# EXPRESS_BYOG_Shield.net
KiCad netlist of a schematic drawn in EAGLE
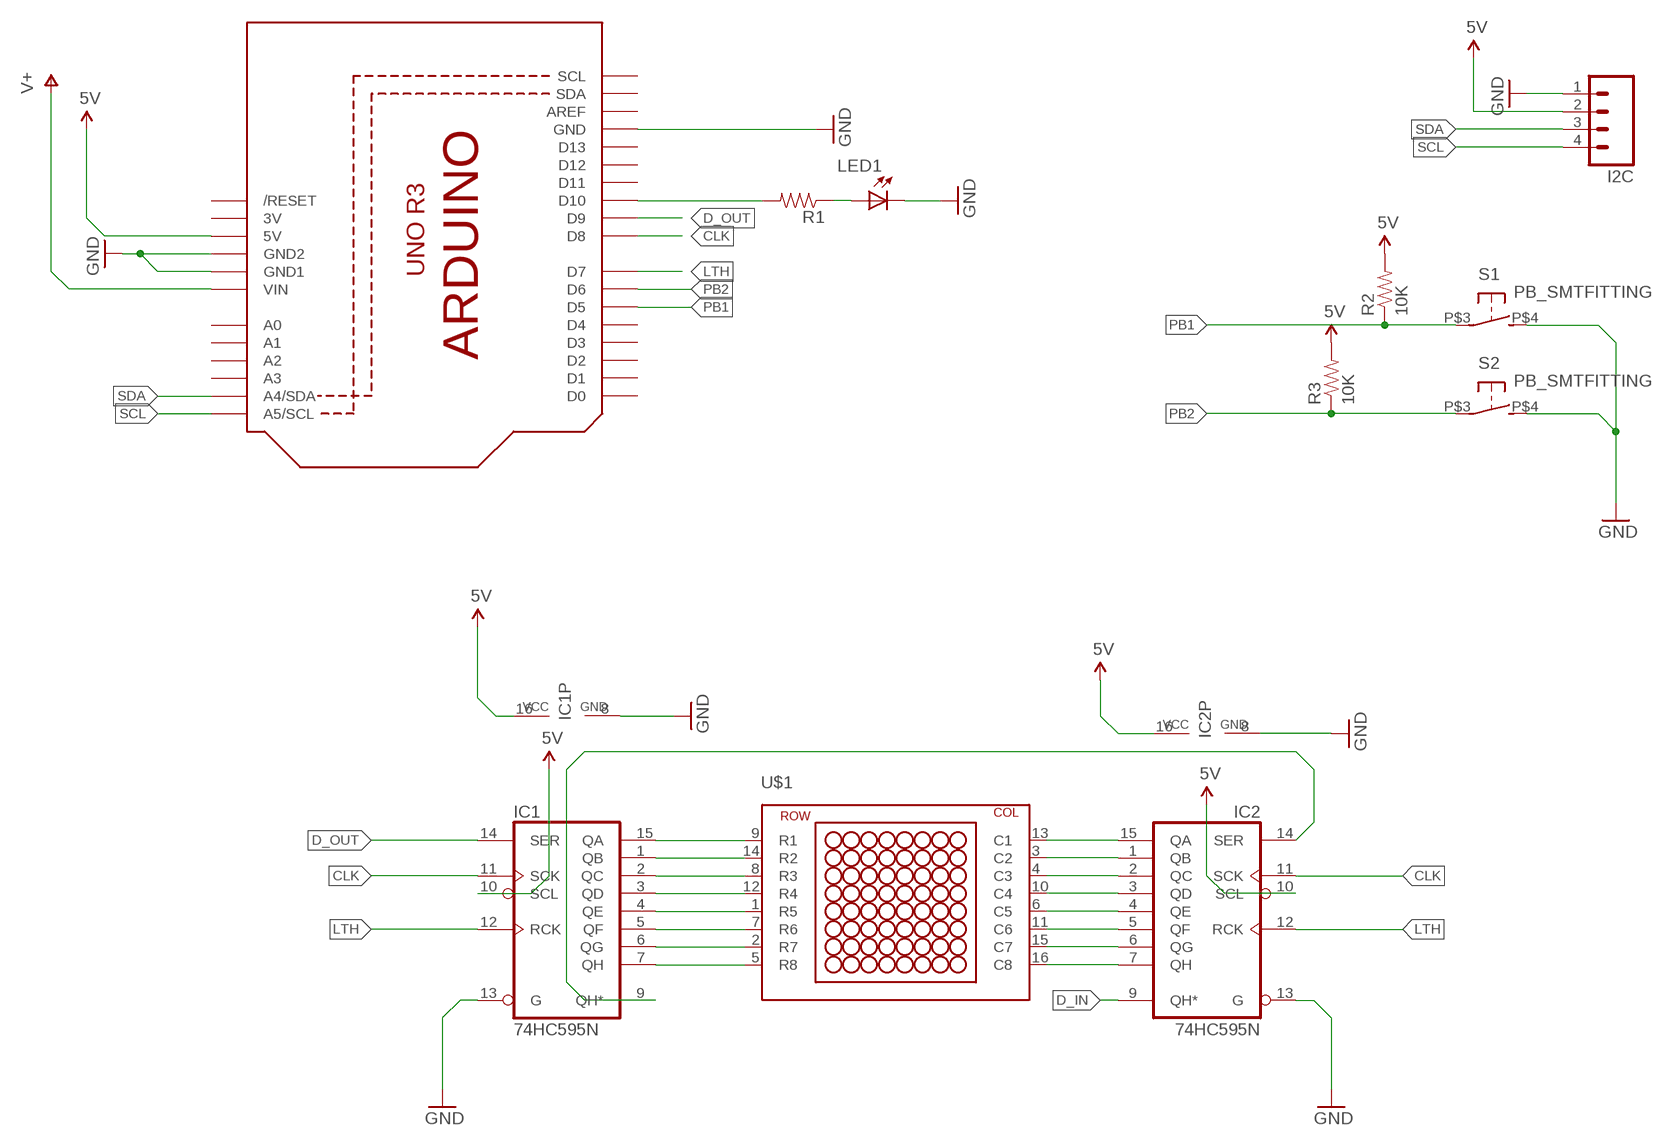
[diagram p0: schematic, sheet 1]

(export (version "E")
  (design (tool "Eeschema 10.0.6"))
  (components
    (comp (ref "I2C")
      (value "M04PTH")
      (footprint "eagle-import:1X04")
      (libsource (lib "eagle-import") (part "M04PTH"))
    )
    (comp (ref "IC1")
      (value "74HC595N")
      (footprint "eagle-import:DIL16")
      (libsource (lib "eagle-import") (part "74595NHC"))
    )
    (comp (ref "IC2")
      (value "74HC595N")
      (footprint "eagle-import:DIL16")
      (libsource (lib "eagle-import") (part "74595NHC"))
    )
    (comp (ref "LED1")
      (value "LED/0805")
      (footprint "eagle-import:CHIP-LED0805")
      (libsource (lib "eagle-import") (part "LED/0805"))
    )
    (comp (ref "R1")
      (value "RESISTOR0805-RES")
      (footprint "eagle-import:0805")
      (libsource (lib "eagle-import") (part "RESISTOR0805-RES"))
    )
    (comp (ref "R2")
      (value "10K")
      (footprint "eagle-import:0805")
      (libsource (lib "eagle-import") (part "RESISTOR0805-RES"))
    )
    (comp (ref "R3")
      (value "10K")
      (footprint "eagle-import:0805")
      (libsource (lib "eagle-import") (part "RESISTOR0805-RES"))
    )
    (comp (ref "S1")
      (value "PB_SMTFITTING")
      (footprint "eagle-import:PB_SMT_TIGHT")
      (libsource (lib "eagle-import") (part "PB_SMTFITTING"))
    )
    (comp (ref "S2")
      (value "PB_SMTFITTING")
      (footprint "eagle-import:PB_SMT_TIGHT")
      (libsource (lib "eagle-import") (part "PB_SMTFITTING"))
    )
    (comp (ref "U$1")
      (value "8X8DM_2088AS")
      (footprint "eagle-import:8X8DM_2088AS")
      (libsource (lib "eagle-import") (part "8X8DM_2088AS"))
    )
    (comp (ref "U1")
      (value "ARDUINOR3-NOIOREF-NOTEXT")
      (footprint "eagle-import:ARDUINOR3-NOTEXT-NOIOREF")
      (libsource (lib "eagle-import") (part "ARDUINOR3-NOIOREF-NOTEXT"))
    )
  )
  (nets
    (net (code "1") (name "/3V") (class "Default")
      (node (ref "U1") (pin "3V") (pinfunction "3V_3V") (pintype "power_in"))
    )
    (net (code "2") (name "5V") (class "Default")
      (node (ref "I2C") (pin "2") (pinfunction "2_2") (pintype "passive"))
      (node (ref "IC1") (pin "10") (pinfunction "SCL_10") (pintype "input"))
      (node (ref "IC1") (pin "16") (pinfunction "VCC_16") (pintype "power_in"))
      (node (ref "IC2") (pin "10") (pinfunction "SCL_10") (pintype "input"))
      (node (ref "IC2") (pin "16") (pinfunction "VCC_16") (pintype "power_in"))
      (node (ref "R2") (pin "2") (pinfunction "2_2") (pintype "passive"))
      (node (ref "R3") (pin "2") (pinfunction "2_2") (pintype "passive"))
      (node (ref "U1") (pin "5V") (pinfunction "5V_5V") (pintype "power_in"))
    )
    (net (code "3") (name "CLK") (class "Default")
      (node (ref "IC1") (pin "11") (pinfunction "SCK_11") (pintype "input"))
      (node (ref "IC2") (pin "11") (pinfunction "SCK_11") (pintype "input"))
      (node (ref "U1") (pin "D8") (pinfunction "D8_D8") (pintype "bidirectional"))
    )
    (net (code "4") (name "D_IN") (class "Default")
      (node (ref "IC2") (pin "9") (pinfunction "QH*_9") (pintype "tri_state"))
    )
    (net (code "5") (name "D_OUT") (class "Default")
      (node (ref "IC1") (pin "14") (pinfunction "SER_14") (pintype "input"))
      (node (ref "U1") (pin "D9") (pinfunction "D9_D9") (pintype "bidirectional"))
    )
    (net (code "6") (name "GND") (class "Default")
      (node (ref "I2C") (pin "1") (pinfunction "1_1") (pintype "passive"))
      (node (ref "IC1") (pin "13") (pinfunction "G_13") (pintype "input"))
      (node (ref "IC1") (pin "8") (pinfunction "GND_8") (pintype "power_in"))
      (node (ref "IC2") (pin "13") (pinfunction "G_13") (pintype "input"))
      (node (ref "IC2") (pin "8") (pinfunction "GND_8") (pintype "power_in"))
      (node (ref "LED1") (pin "C") (pinfunction "C_C") (pintype "passive"))
      (node (ref "S1") (pin "P$4") (pinfunction "2_P$4") (pintype "passive"))
      (node (ref "S2") (pin "P$4") (pinfunction "2_P$4") (pintype "passive"))
      (node (ref "U1") (pin "GND") (pinfunction "GND_GND") (pintype "power_in"))
      (node (ref "U1") (pin "GND1") (pinfunction "GND1_GND1") (pintype "power_in"))
      (node (ref "U1") (pin "GND2") (pinfunction "GND2_GND2") (pintype "power_in"))
    )
    (net (code "7") (name "LTH") (class "Default")
      (node (ref "IC1") (pin "12") (pinfunction "RCK_12") (pintype "input"))
      (node (ref "IC2") (pin "12") (pinfunction "RCK_12") (pintype "input"))
      (node (ref "U1") (pin "D7") (pinfunction "D7_D7") (pintype "bidirectional"))
    )
    (net (code "8") (name "Net-(IC1A-QA)") (class "Default")
      (node (ref "IC1") (pin "15") (pinfunction "QA_15") (pintype "tri_state"))
      (node (ref "U$1") (pin "9") (pinfunction "R1_9") (pintype "bidirectional"))
    )
    (net (code "9") (name "Net-(IC1A-QB)") (class "Default")
      (node (ref "IC1") (pin "1") (pinfunction "QB_1") (pintype "tri_state"))
      (node (ref "U$1") (pin "14") (pinfunction "R2_14") (pintype "bidirectional"))
    )
    (net (code "10") (name "Net-(IC1A-QC)") (class "Default")
      (node (ref "IC1") (pin "2") (pinfunction "QC_2") (pintype "tri_state"))
      (node (ref "U$1") (pin "8") (pinfunction "R3_8") (pintype "bidirectional"))
    )
    (net (code "11") (name "Net-(IC1A-QD)") (class "Default")
      (node (ref "IC1") (pin "3") (pinfunction "QD_3") (pintype "tri_state"))
      (node (ref "U$1") (pin "12") (pinfunction "R4_12") (pintype "bidirectional"))
    )
    (net (code "12") (name "Net-(IC1A-QE)") (class "Default")
      (node (ref "IC1") (pin "4") (pinfunction "QE_4") (pintype "tri_state"))
      (node (ref "U$1") (pin "1") (pinfunction "R5_1") (pintype "bidirectional"))
    )
    (net (code "13") (name "Net-(IC1A-QF)") (class "Default")
      (node (ref "IC1") (pin "5") (pinfunction "QF_5") (pintype "tri_state"))
      (node (ref "U$1") (pin "7") (pinfunction "R6_7") (pintype "bidirectional"))
    )
    (net (code "14") (name "Net-(IC1A-QG)") (class "Default")
      (node (ref "IC1") (pin "6") (pinfunction "QG_6") (pintype "tri_state"))
      (node (ref "U$1") (pin "2") (pinfunction "R7_2") (pintype "bidirectional"))
    )
    (net (code "15") (name "Net-(IC1A-QH)") (class "Default")
      (node (ref "IC1") (pin "7") (pinfunction "QH_7") (pintype "tri_state"))
      (node (ref "U$1") (pin "5") (pinfunction "R8_5") (pintype "bidirectional"))
    )
    (net (code "16") (name "Net-(IC1A-QH*)") (class "Default")
      (node (ref "IC1") (pin "9") (pinfunction "QH*_9") (pintype "tri_state"))
      (node (ref "IC2") (pin "14") (pinfunction "SER_14") (pintype "input"))
    )
    (net (code "17") (name "Net-(IC2A-QA)") (class "Default")
      (node (ref "IC2") (pin "15") (pinfunction "QA_15") (pintype "tri_state"))
      (node (ref "U$1") (pin "13") (pinfunction "C1_13") (pintype "bidirectional"))
    )
    (net (code "18") (name "Net-(IC2A-QB)") (class "Default")
      (node (ref "IC2") (pin "1") (pinfunction "QB_1") (pintype "tri_state"))
      (node (ref "U$1") (pin "3") (pinfunction "C2_3") (pintype "bidirectional"))
    )
    (net (code "19") (name "Net-(IC2A-QC)") (class "Default")
      (node (ref "IC2") (pin "2") (pinfunction "QC_2") (pintype "tri_state"))
      (node (ref "U$1") (pin "4") (pinfunction "C3_4") (pintype "bidirectional"))
    )
    (net (code "20") (name "Net-(IC2A-QD)") (class "Default")
      (node (ref "IC2") (pin "3") (pinfunction "QD_3") (pintype "tri_state"))
      (node (ref "U$1") (pin "10") (pinfunction "C4_10") (pintype "bidirectional"))
    )
    (net (code "21") (name "Net-(IC2A-QE)") (class "Default")
      (node (ref "IC2") (pin "4") (pinfunction "QE_4") (pintype "tri_state"))
      (node (ref "U$1") (pin "6") (pinfunction "C5_6") (pintype "bidirectional"))
    )
    (net (code "22") (name "Net-(IC2A-QF)") (class "Default")
      (node (ref "IC2") (pin "5") (pinfunction "QF_5") (pintype "tri_state"))
      (node (ref "U$1") (pin "11") (pinfunction "C6_11") (pintype "bidirectional"))
    )
    (net (code "23") (name "Net-(IC2A-QG)") (class "Default")
      (node (ref "IC2") (pin "6") (pinfunction "QG_6") (pintype "tri_state"))
      (node (ref "U$1") (pin "15") (pinfunction "C7_15") (pintype "bidirectional"))
    )
    (net (code "24") (name "Net-(IC2A-QH)") (class "Default")
      (node (ref "IC2") (pin "7") (pinfunction "QH_7") (pintype "tri_state"))
      (node (ref "U$1") (pin "16") (pinfunction "C8_16") (pintype "bidirectional"))
    )
    (net (code "25") (name "Net-(LED1-PadA)") (class "Default")
      (node (ref "LED1") (pin "A") (pinfunction "A_A") (pintype "passive"))
      (node (ref "R1") (pin "1") (pinfunction "1_1") (pintype "passive"))
    )
    (net (code "26") (name "Net-(R1-Pad2)") (class "Default")
      (node (ref "R1") (pin "2") (pinfunction "2_2") (pintype "passive"))
      (node (ref "U1") (pin "D10") (pinfunction "D10_D10") (pintype "bidirectional"))
    )
    (net (code "27") (name "PB1") (class "Default")
      (node (ref "R2") (pin "1") (pinfunction "1_1") (pintype "passive"))
      (node (ref "S1") (pin "P$3") (pinfunction "1_P$3") (pintype "passive"))
      (node (ref "U1") (pin "D5") (pinfunction "D5_D5") (pintype "bidirectional"))
    )
    (net (code "28") (name "PB2") (class "Default")
      (node (ref "R3") (pin "1") (pinfunction "1_1") (pintype "passive"))
      (node (ref "S2") (pin "P$3") (pinfunction "1_P$3") (pintype "passive"))
      (node (ref "U1") (pin "D6") (pinfunction "D6_D6") (pintype "bidirectional"))
    )
    (net (code "29") (name "SCL") (class "Default")
      (node (ref "I2C") (pin "4") (pinfunction "4_4") (pintype "passive"))
      (node (ref "U1") (pin "A5") (pinfunction "A5/SCL_A5") (pintype "bidirectional"))
    )
    (net (code "30") (name "SDA") (class "Default")
      (node (ref "I2C") (pin "3") (pinfunction "3_3") (pintype "passive"))
      (node (ref "U1") (pin "A4") (pinfunction "A4/SDA_A4") (pintype "bidirectional"))
    )
    (net (code "31") (name "V+") (class "Default")
      (node (ref "U1") (pin "VIN") (pinfunction "VIN_VIN") (pintype "power_in"))
    )
    (net (code "32") (name "unconnected-(U1-PadA0)") (class "Default")
      (node (ref "U1") (pin "A0") (pinfunction "A0_A0") (pintype "bidirectional"))
    )
    (net (code "33") (name "unconnected-(U1-PadA1)") (class "Default")
      (node (ref "U1") (pin "A1") (pinfunction "A1_A1") (pintype "bidirectional"))
    )
    (net (code "34") (name "unconnected-(U1-PadA2)") (class "Default")
      (node (ref "U1") (pin "A2") (pinfunction "A2_A2") (pintype "bidirectional"))
    )
    (net (code "35") (name "unconnected-(U1-PadA3)") (class "Default")
      (node (ref "U1") (pin "A3") (pinfunction "A3_A3") (pintype "bidirectional"))
    )
    (net (code "36") (name "unconnected-(U1-PadAREF)") (class "Default")
      (node (ref "U1") (pin "AREF") (pinfunction "AREF_AREF") (pintype "bidirectional"))
    )
    (net (code "37") (name "unconnected-(U1-PadD0)") (class "Default")
      (node (ref "U1") (pin "D0") (pinfunction "D0_D0") (pintype "bidirectional"))
    )
    (net (code "38") (name "unconnected-(U1-PadD1)") (class "Default")
      (node (ref "U1") (pin "D1") (pinfunction "D1_D1") (pintype "bidirectional"))
    )
    (net (code "39") (name "unconnected-(U1-PadD2)") (class "Default")
      (node (ref "U1") (pin "D2") (pinfunction "D2_D2") (pintype "bidirectional"))
    )
    (net (code "40") (name "unconnected-(U1-PadD3)") (class "Default")
      (node (ref "U1") (pin "D3") (pinfunction "D3_D3") (pintype "bidirectional"))
    )
    (net (code "41") (name "unconnected-(U1-PadD4)") (class "Default")
      (node (ref "U1") (pin "D4") (pinfunction "D4_D4") (pintype "bidirectional"))
    )
    (net (code "42") (name "unconnected-(U1-PadD11)") (class "Default")
      (node (ref "U1") (pin "D11") (pinfunction "D11_D11") (pintype "bidirectional"))
    )
    (net (code "43") (name "unconnected-(U1-PadD12)") (class "Default")
      (node (ref "U1") (pin "D12") (pinfunction "D12_D12") (pintype "bidirectional"))
    )
    (net (code "44") (name "unconnected-(U1-PadD13)") (class "Default")
      (node (ref "U1") (pin "D13") (pinfunction "D13_D13") (pintype "bidirectional"))
    )
    (net (code "45") (name "unconnected-(U1-PadSCL)") (class "Default")
      (node (ref "U1") (pin "SCL") (pinfunction "SCL_SCL") (pintype "bidirectional"))
    )
    (net (code "46") (name "unconnected-(U1-PadSDA)") (class "Default")
      (node (ref "U1") (pin "SDA") (pinfunction "SDA_SDA") (pintype "bidirectional"))
    )
    (net (code "47") (name "unconnected-(U1-{slash}RESET-PadRESET)") (class "Default")
      (node (ref "U1") (pin "RESET") (pinfunction "/RESET_RESET") (pintype "bidirectional"))
    )
  )
)
